# Channel.net
KiCad netlist of a schematic drawn in Altium Designer
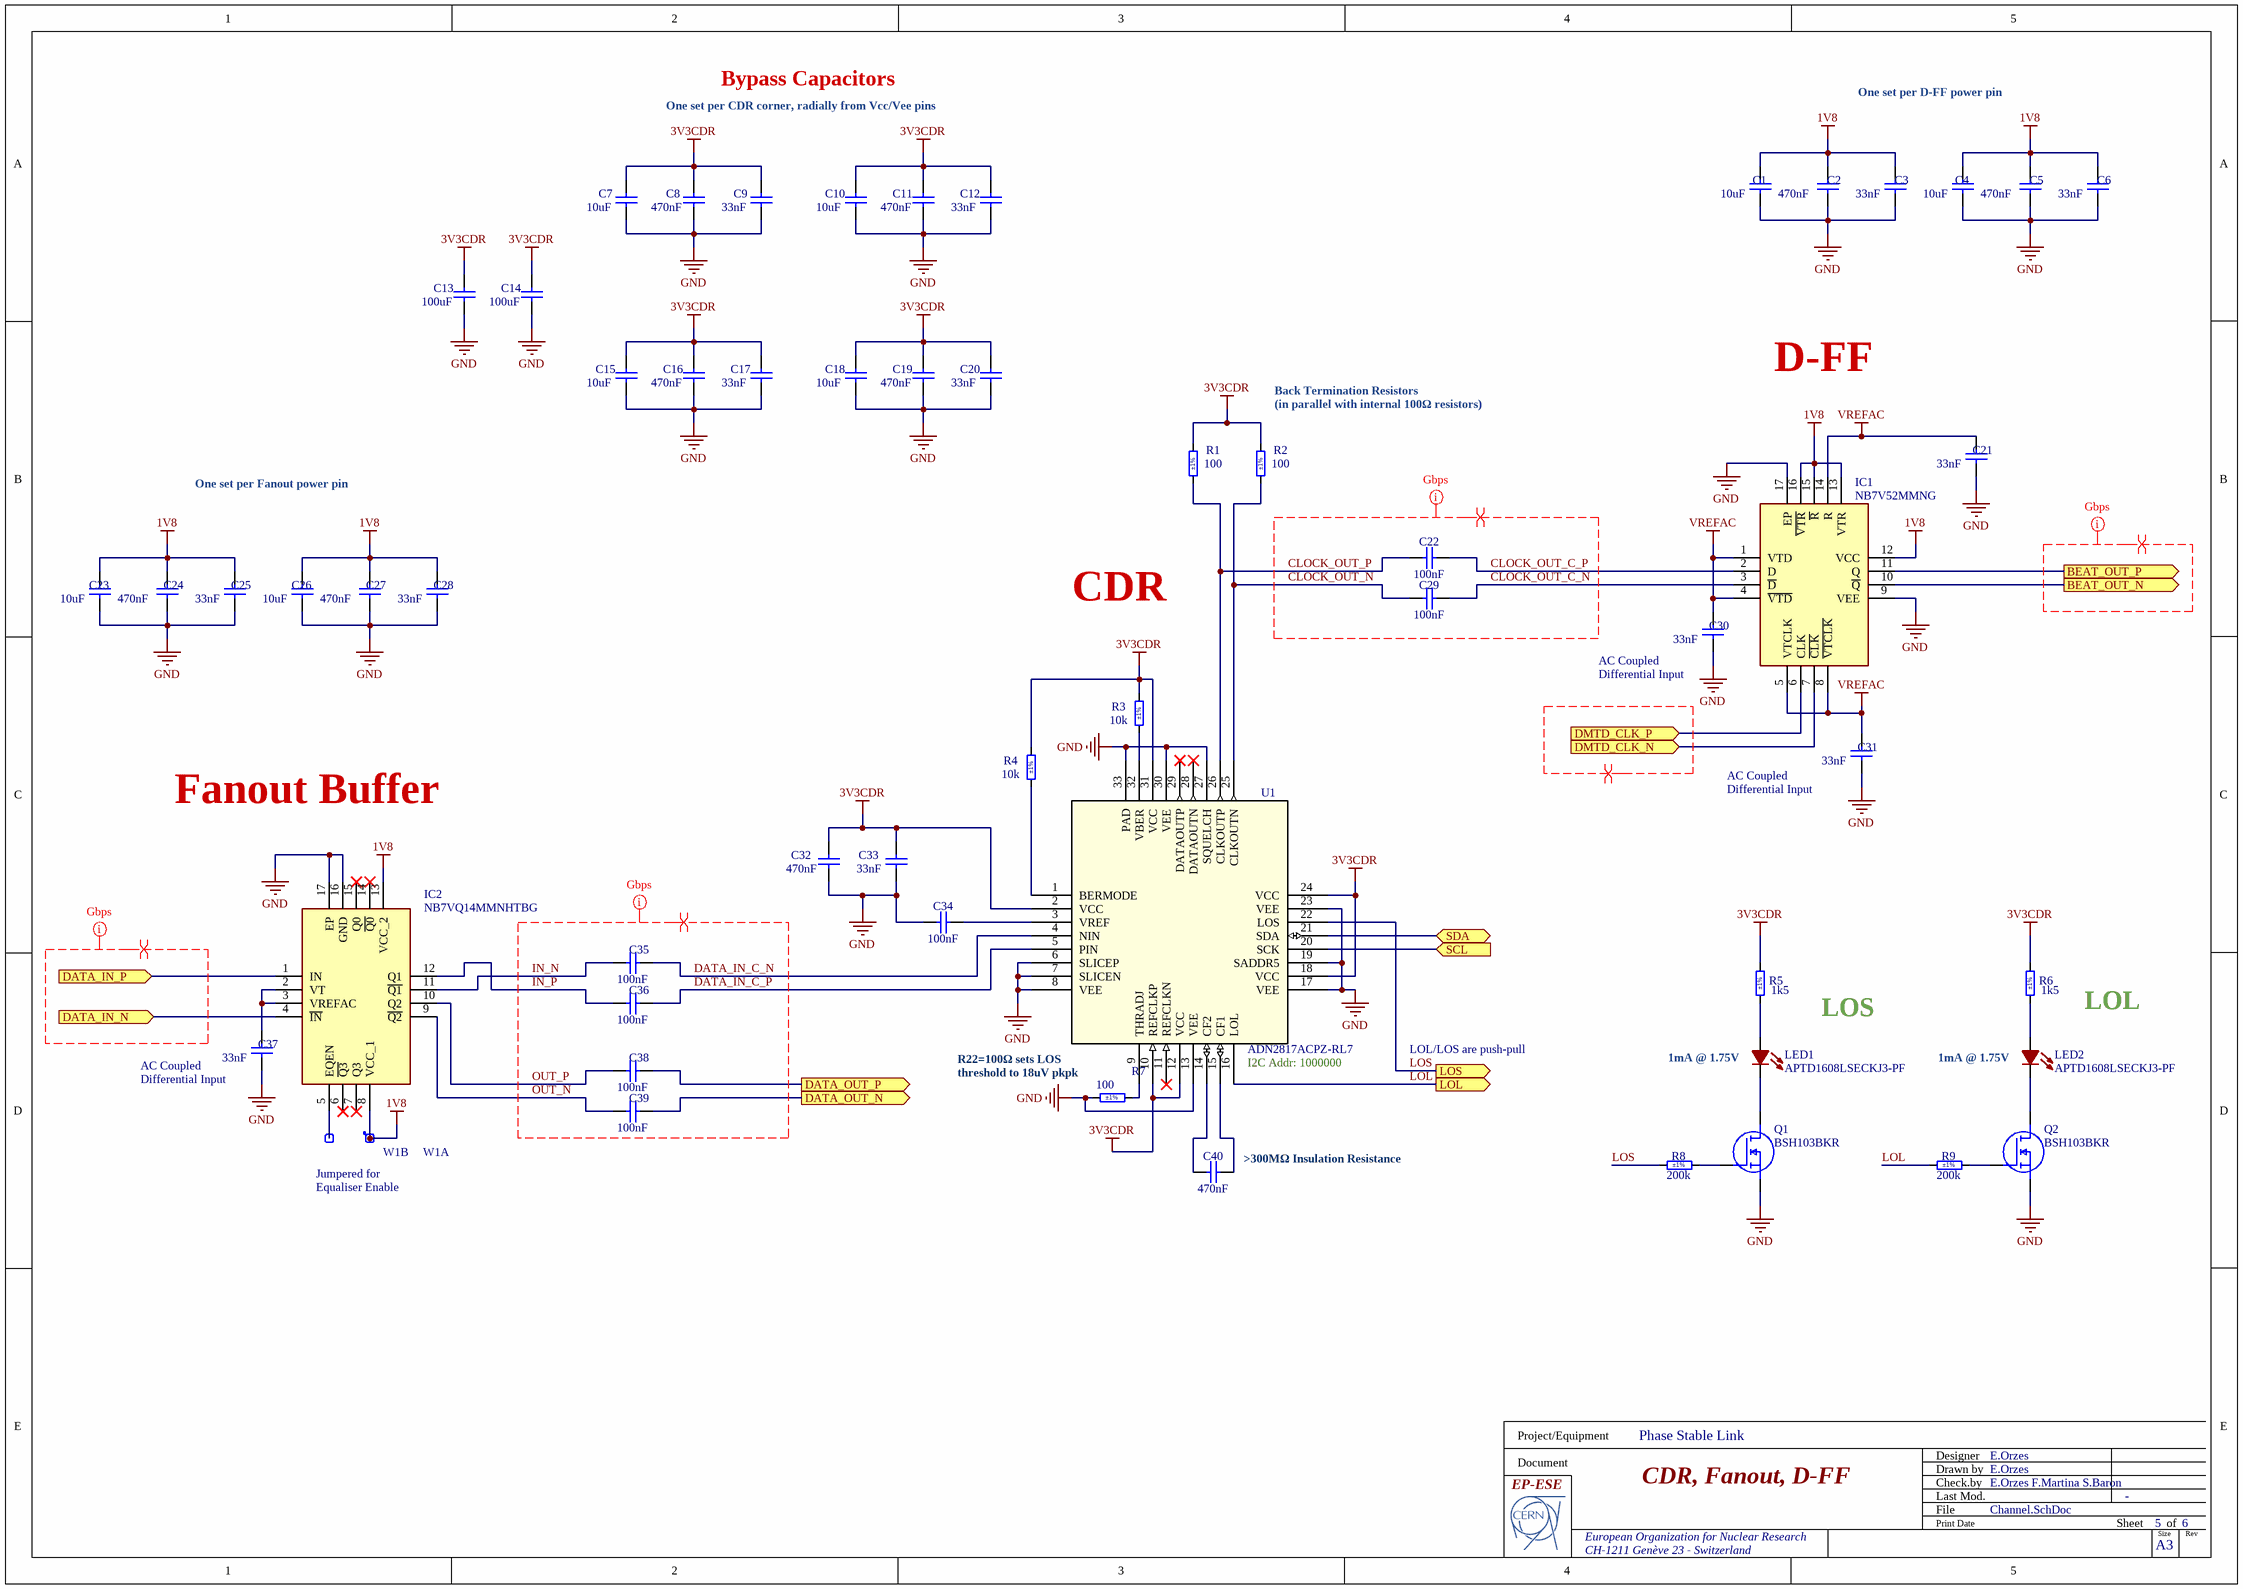
[diagram p0: Channel.SchDoc]

(export (version "E")
  (design (tool "Eeschema 10.0.6"))
  (components
    (comp (ref "C1")
      (value "10uF")
      (footprint "CAPC1608X87N")
      (description "GRM188D71A106KA73")
      (fields
        (field (name "PART NUMBER") "CC0603_10UF_6.3V_20%_X5R")
        (field (name "VOLTAGE") "6.3V")
        (field (name "AUTHOR") "CERN DEM JLC")
      )
      (libsource (lib "Capacitors") (part "Capacitor - non polarized"))
    )
    (comp (ref "C2")
      (value "470nF")
      (footprint "CAPC0510X04N")
      (description "LLL153C70G474ME17")
      (libsource (lib "auxiliary_library") (part "Capacitor - non polarized"))
    )
    (comp (ref "C3")
      (value "33nF")
      (footprint "LLL03TR61E333KE01")
      (description "LLL03TR61E333KE01")
      (libsource (lib "auxiliary_library") (part "Capacitor - non polarized"))
    )
    (comp (ref "C4")
      (value "10uF")
      (footprint "CAPC1608X87N")
      (description "GRM188D71A106KA73")
      (fields
        (field (name "PART NUMBER") "CC0603_10UF_6.3V_20%_X5R")
        (field (name "VOLTAGE") "6.3V")
        (field (name "AUTHOR") "CERN DEM JLC")
      )
      (libsource (lib "Capacitors") (part "Capacitor - non polarized"))
    )
    (comp (ref "C5")
      (value "470nF")
      (footprint "CAPC0510X04N")
      (description "LLL153C70G474ME17")
      (libsource (lib "auxiliary_library") (part "Capacitor - non polarized"))
    )
    (comp (ref "C6")
      (value "33nF")
      (footprint "LLL03TR61E333KE01")
      (description "LLL03TR61E333KE01")
      (libsource (lib "auxiliary_library") (part "Capacitor - non polarized"))
    )
    (comp (ref "C7")
      (value "10uF")
      (footprint "CAPC1608X87N")
      (description "GRM188D71A106KA73")
      (fields
        (field (name "PART NUMBER") "CC0603_10UF_6.3V_20%_X5R")
        (field (name "VOLTAGE") "6.3V")
        (field (name "AUTHOR") "CERN DEM JLC")
      )
      (libsource (lib "Capacitors") (part "Capacitor - non polarized"))
    )
    (comp (ref "C8")
      (value "470nF")
      (footprint "CAPC0510X04N")
      (description "LLL153C70G474ME17")
      (libsource (lib "auxiliary_library") (part "Capacitor - non polarized"))
    )
    (comp (ref "C9")
      (value "33nF")
      (footprint "LLL03TR61E333KE01")
      (description "LLL03TR61E333KE01")
      (libsource (lib "auxiliary_library") (part "Capacitor - non polarized"))
    )
    (comp (ref "C10")
      (value "10uF")
      (footprint "CAPC1608X87N")
      (description "GRM188D71A106KA73")
      (fields
        (field (name "PART NUMBER") "CC0603_10UF_6.3V_20%_X5R")
        (field (name "VOLTAGE") "6.3V")
        (field (name "AUTHOR") "CERN DEM JLC")
      )
      (libsource (lib "Capacitors") (part "Capacitor - non polarized"))
    )
    (comp (ref "C11")
      (value "470nF")
      (footprint "CAPC0510X04N")
      (description "LLL153C70G474ME17")
      (libsource (lib "auxiliary_library") (part "Capacitor - non polarized"))
    )
    (comp (ref "C12")
      (value "33nF")
      (footprint "LLL03TR61E333KE01")
      (description "LLL03TR61E333KE01")
      (libsource (lib "auxiliary_library") (part "Capacitor - non polarized"))
    )
    (comp (ref "C13")
      (value "100uF")
      (footprint "CAPC3225X270N")
      (description "GRM32EC70J107ME15")
      (fields
        (field (name "PART NUMBER") "CC1210_100UF_6.3V_20%_X7U")
        (field (name "VOLTAGE") "6.3V")
        (field (name "AUTHOR") "CERN DEM MR")
      )
      (libsource (lib "Capacitors") (part "Capacitor - non polarized"))
    )
    (comp (ref "C14")
      (value "100uF")
      (footprint "CAPC3225X270N")
      (description "GRM32EC70J107ME15")
      (fields
        (field (name "PART NUMBER") "CC1210_100UF_6.3V_20%_X7U")
        (field (name "VOLTAGE") "6.3V")
        (field (name "AUTHOR") "CERN DEM MR")
      )
      (libsource (lib "Capacitors") (part "Capacitor - non polarized"))
    )
    (comp (ref "C15")
      (value "10uF")
      (footprint "CAPC1608X87N")
      (description "GRM188D71A106KA73")
      (fields
        (field (name "PART NUMBER") "CC0603_10UF_6.3V_20%_X5R")
        (field (name "VOLTAGE") "6.3V")
        (field (name "AUTHOR") "CERN DEM JLC")
      )
      (libsource (lib "Capacitors") (part "Capacitor - non polarized"))
    )
    (comp (ref "C16")
      (value "470nF")
      (footprint "CAPC0510X04N")
      (description "LLL153C70G474ME17")
      (libsource (lib "auxiliary_library") (part "Capacitor - non polarized"))
    )
    (comp (ref "C17")
      (value "33nF")
      (footprint "LLL03TR61E333KE01")
      (description "LLL03TR61E333KE01")
      (libsource (lib "auxiliary_library") (part "Capacitor - non polarized"))
    )
    (comp (ref "C18")
      (value "10uF")
      (footprint "CAPC1608X87N")
      (description "GRM188D71A106KA73")
      (fields
        (field (name "PART NUMBER") "CC0603_10UF_6.3V_20%_X5R")
        (field (name "VOLTAGE") "6.3V")
        (field (name "AUTHOR") "CERN DEM JLC")
      )
      (libsource (lib "Capacitors") (part "Capacitor - non polarized"))
    )
    (comp (ref "C19")
      (value "470nF")
      (footprint "CAPC0510X04N")
      (description "LLL153C70G474ME17")
      (libsource (lib "auxiliary_library") (part "Capacitor - non polarized"))
    )
    (comp (ref "C20")
      (value "33nF")
      (footprint "LLL03TR61E333KE01")
      (description "LLL03TR61E333KE01")
      (libsource (lib "auxiliary_library") (part "Capacitor - non polarized"))
    )
    (comp (ref "C21")
      (value "33nF")
      (footprint "LLL03TR61E333KE01")
      (description "LLL03TR61E333KE01")
      (libsource (lib "auxiliary_library") (part "Capacitor - non polarized"))
    )
    (comp (ref "C22")
      (value "100nF")
      (footprint "CAPC0603X33N")
      (description "Non-polarised capacitor")
      (fields
        (field (name "PART NUMBER") "CC0201_100NF_6.3V_10%_X7R")
        (field (name "VOLTAGE") "6.3V")
        (field (name "AUTHOR") "CERN DEM BC")
      )
      (libsource (lib "Capacitors") (part "Capacitor - non polarized"))
    )
    (comp (ref "C23")
      (value "10uF")
      (footprint "CAPC1608X87N")
      (description "GRM188D71A106KA73")
      (fields
        (field (name "PART NUMBER") "CC0603_10UF_6.3V_20%_X5R")
        (field (name "VOLTAGE") "6.3V")
        (field (name "AUTHOR") "CERN DEM JLC")
      )
      (libsource (lib "Capacitors") (part "Capacitor - non polarized"))
    )
    (comp (ref "C24")
      (value "470nF")
      (footprint "CAPC0510X04N")
      (description "LLL153C70G474ME17")
      (libsource (lib "auxiliary_library") (part "Capacitor - non polarized"))
    )
    (comp (ref "C25")
      (value "33nF")
      (footprint "LLL03TR61E333KE01")
      (description "LLL03TR61E333KE01")
      (libsource (lib "auxiliary_library") (part "Capacitor - non polarized"))
    )
    (comp (ref "C26")
      (value "10uF")
      (footprint "CAPC1608X87N")
      (description "GRM188D71A106KA73")
      (fields
        (field (name "PART NUMBER") "CC0603_10UF_6.3V_20%_X5R")
        (field (name "VOLTAGE") "6.3V")
        (field (name "AUTHOR") "CERN DEM JLC")
      )
      (libsource (lib "Capacitors") (part "Capacitor - non polarized"))
    )
    (comp (ref "C27")
      (value "470nF")
      (footprint "CAPC0510X04N")
      (description "LLL153C70G474ME17")
      (libsource (lib "auxiliary_library") (part "Capacitor - non polarized"))
    )
    (comp (ref "C28")
      (value "33nF")
      (footprint "LLL03TR61E333KE01")
      (description "LLL03TR61E333KE01")
      (libsource (lib "auxiliary_library") (part "Capacitor - non polarized"))
    )
    (comp (ref "C29")
      (value "100nF")
      (footprint "CAPC0603X33N")
      (description "Non-polarised capacitor")
      (fields
        (field (name "PART NUMBER") "CC0201_100NF_6.3V_10%_X7R")
        (field (name "VOLTAGE") "6.3V")
        (field (name "AUTHOR") "CERN DEM BC")
      )
      (libsource (lib "Capacitors") (part "Capacitor - non polarized"))
    )
    (comp (ref "C30")
      (value "33nF")
      (footprint "LLL03TR61E333KE01")
      (description "LLL03TR61E333KE01")
      (libsource (lib "auxiliary_library") (part "Capacitor - non polarized"))
    )
    (comp (ref "C31")
      (value "33nF")
      (footprint "LLL03TR61E333KE01")
      (description "LLL03TR61E333KE01")
      (libsource (lib "auxiliary_library") (part "Capacitor - non polarized"))
    )
    (comp (ref "C32")
      (value "470nF")
      (footprint "CAPC0510X04N")
      (description "LLL153C70G474ME17")
      (libsource (lib "auxiliary_library") (part "Capacitor - non polarized"))
    )
    (comp (ref "C33")
      (value "33nF")
      (footprint "LLL03TR61E333KE01")
      (description "LLL03TR61E333KE01")
      (libsource (lib "auxiliary_library") (part "Capacitor - non polarized"))
    )
    (comp (ref "C34")
      (value "100nF")
      (footprint "CAPC0603X33N")
      (description "Non-polarised capacitor")
      (fields
        (field (name "PART NUMBER") "CC0201_100NF_6.3V_10%_X7R")
        (field (name "VOLTAGE") "6.3V")
        (field (name "AUTHOR") "CERN DEM BC")
      )
      (libsource (lib "Capacitors") (part "Capacitor - non polarized"))
    )
    (comp (ref "C35")
      (value "100nF")
      (footprint "CAPC0603X33N")
      (description "Non-polarised capacitor")
      (fields
        (field (name "PART NUMBER") "CC0201_100NF_6.3V_10%_X7R")
        (field (name "VOLTAGE") "6.3V")
        (field (name "AUTHOR") "CERN DEM BC")
      )
      (libsource (lib "Capacitors") (part "Capacitor - non polarized"))
    )
    (comp (ref "C36")
      (value "100nF")
      (footprint "CAPC0603X33N")
      (description "Non-polarised capacitor")
      (fields
        (field (name "PART NUMBER") "CC0201_100NF_6.3V_10%_X7R")
        (field (name "VOLTAGE") "6.3V")
        (field (name "AUTHOR") "CERN DEM BC")
      )
      (libsource (lib "Capacitors") (part "Capacitor - non polarized"))
    )
    (comp (ref "C37")
      (value "33nF")
      (footprint "LLL03TR61E333KE01")
      (description "LLL03TR61E333KE01")
      (libsource (lib "auxiliary_library") (part "Capacitor - non polarized"))
    )
    (comp (ref "C38")
      (value "100nF")
      (footprint "CAPC0603X33N")
      (description "Non-polarised capacitor")
      (fields
        (field (name "PART NUMBER") "CC0201_100NF_6.3V_10%_X7R")
        (field (name "VOLTAGE") "6.3V")
        (field (name "AUTHOR") "CERN DEM BC")
      )
      (libsource (lib "Capacitors") (part "Capacitor - non polarized"))
    )
    (comp (ref "C39")
      (value "100nF")
      (footprint "CAPC0603X33N")
      (description "Non-polarised capacitor")
      (fields
        (field (name "PART NUMBER") "CC0201_100NF_6.3V_10%_X7R")
        (field (name "VOLTAGE") "6.3V")
        (field (name "AUTHOR") "CERN DEM BC")
      )
      (libsource (lib "Capacitors") (part "Capacitor - non polarized"))
    )
    (comp (ref "C40")
      (value "470nF")
      (footprint "CAPC2013X140N")
      (description "GCM21BR71H474KA55L")
      (fields
        (field (name "PART NUMBER") "CC0805_470NF_50V_10%_X7R_MURATA_GCM21BR71H474KA55L")
        (field (name "VOLTAGE") "50V")
        (field (name "AUTHOR") "CERN DEM JLC")
      )
      (libsource (lib "Capacitors") (part "Capacitor - non polarized"))
    )
    (comp (ref "IC1")
      (value "NB7V52MMNG")
      (footprint "SamacSys:QFN50P300X300X100-17N")
      (description "Integrated Circuit")
      (fields (field (name "MOUSER PART NUMBER") "863-NB7V52MMNG"))
      (libsource (lib "SamacSys") (part "NB7V52MMNG"))
    )
    (comp (ref "IC2")
      (value "NB7VQ14MMNHTBG")
      (footprint "SamacSys:QFN50P300X300X100-17N")
      (description "Integrated Circuit")
      (fields (field (name "MOUSER PART NUMBER") "863-NB7VQ14MMNHTBG"))
      (libsource (lib "*") (part "NB7VQ14MMNHTBG"))
    )
    (comp (ref "LED1")
      (value "APTD1608LSECKJ3-PF")
      (footprint "APTD1608LSECKJ3-PF:LED_APTD1608LSECKJ3-PF_KNB")
      (description "Led Red 0603 2mA 1.8V 50mcd 84mW")
      (libsource (lib "APTD1608LSECKJ3-PF") (part "APTD1608LSECKJ3-PF"))
    )
    (comp (ref "LED2")
      (value "APTD1608LSECKJ3-PF")
      (footprint "APTD1608LSECKJ3-PF:LED_APTD1608LSECKJ3-PF_KNB")
      (description "Led Red 0603 2mA 1.8V 50mcd 84mW")
      (libsource (lib "APTD1608LSECKJ3-PF") (part "APTD1608LSECKJ3-PF"))
    )
    (comp (ref "Q1")
      (value "BSH103BKR")
      (footprint "SamacSys:SOT95P230X110-3N")
      (description "MOSFET (N-Channel)")
      (fields (field (name "MOUSER PART NUMBER") "771-BSH103BKR"))
      (libsource (lib "SamacSys") (part "BSH103BKR"))
    )
    (comp (ref "Q2")
      (value "BSH103BKR")
      (footprint "SamacSys:SOT95P230X110-3N")
      (description "MOSFET (N-Channel)")
      (fields (field (name "MOUSER PART NUMBER") "771-BSH103BKR"))
      (libsource (lib "SamacSys") (part "BSH103BKR"))
    )
    (comp (ref "R1")
      (value "100")
      (footprint "RESC0603X28N")
      (description "Resistor - 1%")
      (fields
        (field (name "TOLERANCE") "±1%")
        (field (name "PART NUMBER") "R0201_100R_1%_0.05W_200PPM")
        (field (name "POWER") "0.05W")
        (field (name "AUTHOR") "CERN DEM JLC")
      )
      (libsource (lib "Resistors") (part "Resistor - 1%"))
    )
    (comp (ref "R2")
      (value "100")
      (footprint "RESC0603X28N")
      (description "Resistor - 1%")
      (fields
        (field (name "TOLERANCE") "±1%")
        (field (name "PART NUMBER") "R0201_100R_1%_0.05W_200PPM")
        (field (name "POWER") "0.05W")
        (field (name "AUTHOR") "CERN DEM JLC")
      )
      (libsource (lib "Resistors") (part "Resistor - 1%"))
    )
    (comp (ref "R3")
      (value "10k")
      (footprint "RESC1005X40N")
      (description "Resistor - 1%")
      (fields
        (field (name "TOLERANCE") "±1%")
        (field (name "PART NUMBER") "R0402_10K_1%_0.0625W_100PPM")
        (field (name "POWER") "0.0625W")
        (field (name "AUTHOR") "CERN DEM JLC")
      )
      (libsource (lib "Resistors") (part "Resistor - 1%"))
    )
    (comp (ref "R4")
      (value "10k")
      (footprint "RESC1005X40N")
      (description "Resistor - 1%")
      (fields
        (field (name "TOLERANCE") "±1%")
        (field (name "PART NUMBER") "R0402_10K_1%_0.0625W_100PPM")
        (field (name "POWER") "0.0625W")
        (field (name "AUTHOR") "CERN DEM JLC")
      )
      (libsource (lib "Resistors") (part "Resistor - 1%"))
    )
    (comp (ref "R5")
      (value "1k5")
      (footprint "RESC1005X40N")
      (description "Resistor - 1%")
      (fields
        (field (name "TOLERANCE") "±1%")
        (field (name "PART NUMBER") "R0402_1K5_1%_0.0625W_100PPM")
        (field (name "POWER") "0.0625W")
        (field (name "AUTHOR") "CERN DEM JLC")
      )
      (libsource (lib "Resistors") (part "Resistor - 1%"))
    )
    (comp (ref "R6")
      (value "1k5")
      (footprint "RESC1005X40N")
      (description "Resistor - 1%")
      (fields
        (field (name "TOLERANCE") "±1%")
        (field (name "PART NUMBER") "R0402_1K5_1%_0.0625W_100PPM")
        (field (name "POWER") "0.0625W")
        (field (name "AUTHOR") "CERN DEM JLC")
      )
      (libsource (lib "Resistors") (part "Resistor - 1%"))
    )
    (comp (ref "R7")
      (value "100")
      (footprint "RESC0603X28N")
      (description "Resistor - 1%")
      (fields
        (field (name "TOLERANCE") "±1%")
        (field (name "PART NUMBER") "R0201_100R_1%_0.05W_200PPM")
        (field (name "POWER") "0.05W")
        (field (name "AUTHOR") "CERN DEM JLC")
      )
      (libsource (lib "Resistors") (part "Resistor - 1%"))
    )
    (comp (ref "R8")
      (value "200k")
      (footprint "RESC1005X40N")
      (description "Resistor - 1%")
      (fields
        (field (name "TOLERANCE") "±1%")
        (field (name "PART NUMBER") "R0402_200K_1%_0.0625W_100PPM")
        (field (name "POWER") "0.0625W")
        (field (name "AUTHOR") "CERN DEM JLC")
      )
      (libsource (lib "Resistors") (part "Resistor - 1%"))
    )
    (comp (ref "R9")
      (value "200k")
      (footprint "RESC1005X40N")
      (description "Resistor - 1%")
      (fields
        (field (name "TOLERANCE") "±1%")
        (field (name "PART NUMBER") "R0402_200K_1%_0.0625W_100PPM")
        (field (name "POWER") "0.0625W")
        (field (name "AUTHOR") "CERN DEM JLC")
      )
      (libsource (lib "Resistors") (part "Resistor - 1%"))
    )
    (comp (ref "U1")
      (value "ADN2817ACPZ-RL7")
      (footprint "CP_32_11_ADI")
      (description "No Description Available")
      (libsource (lib "ADN2817ACPZ-RL7") (part "ADN2817ACPZ-RL7"))
    )
    (comp (ref "W1")
      (value "Header 2")
      (footprint "SAMTEC_HTSW-102-23-L-S")
      (description "2 Mini Wire-Wrap Contact Strip Header")
      (fields
        (field (name "PART NUMBER") "SAMTEC_HTSW-102-23-L-S")
        (field (name "MANUFACTURER") "SAMTEC")
        (field (name "AUTHOR") "CERN DEM JLC")
      )
      (libsource (lib "Connectors") (part "Wire-Wrap Contact x2"))
    )
  )
  (nets
    (net (code "1") (name "/BEAT_OUT_N") (class "Default")
      (node (ref "IC1") (pin "10") (pinfunction "~{Q}_10") (pintype "passive"))
    )
    (net (code "2") (name "/BEAT_OUT_P") (class "Default")
      (node (ref "IC1") (pin "11") (pinfunction "Q_11") (pintype "passive"))
    )
    (net (code "3") (name "/CLOCK_OUT_C_N") (class "Default")
      (node (ref "C29") (pin "2") (pinfunction "2_2") (pintype "passive"))
      (node (ref "IC1") (pin "3") (pinfunction "~{D}_3") (pintype "passive"))
    )
    (net (code "4") (name "/CLOCK_OUT_C_P") (class "Default")
      (node (ref "C22") (pin "2") (pinfunction "2_2") (pintype "passive"))
      (node (ref "IC1") (pin "2") (pinfunction "D_2") (pintype "passive"))
    )
    (net (code "5") (name "/CLOCK_OUT_N") (class "Default")
      (node (ref "C29") (pin "1") (pinfunction "1_1") (pintype "passive"))
      (node (ref "R2") (pin "1") (pinfunction "1_1") (pintype "passive"))
      (node (ref "U1") (pin "25") (pinfunction "CLKOUTN_25") (pintype "output"))
    )
    (net (code "6") (name "/CLOCK_OUT_P") (class "Default")
      (node (ref "C22") (pin "1") (pinfunction "1_1") (pintype "passive"))
      (node (ref "R1") (pin "1") (pinfunction "1_1") (pintype "passive"))
      (node (ref "U1") (pin "26") (pinfunction "CLKOUTP_26") (pintype "output"))
    )
    (net (code "7") (name "/DATA_IN_C_N") (class "Default")
      (node (ref "C35") (pin "2") (pinfunction "2_2") (pintype "passive"))
      (node (ref "U1") (pin "4") (pinfunction "NIN_4") (pintype "passive"))
    )
    (net (code "8") (name "/DATA_IN_C_P") (class "Default")
      (node (ref "C36") (pin "2") (pinfunction "2_2") (pintype "passive"))
      (node (ref "U1") (pin "5") (pinfunction "PIN_5") (pintype "passive"))
    )
    (net (code "9") (name "/DATA_IN_N") (class "Default")
      (node (ref "IC2") (pin "4") (pinfunction "~{IN}_4") (pintype "passive"))
    )
    (net (code "10") (name "/DATA_IN_P") (class "Default")
      (node (ref "IC2") (pin "1") (pinfunction "IN_1") (pintype "passive"))
    )
    (net (code "11") (name "/DATA_OUT_N") (class "Default")
      (node (ref "C39") (pin "2") (pinfunction "2_2") (pintype "passive"))
    )
    (net (code "12") (name "/DATA_OUT_P") (class "Default")
      (node (ref "C38") (pin "2") (pinfunction "2_2") (pintype "passive"))
    )
    (net (code "13") (name "/DMTD_CLK_N") (class "Default")
      (node (ref "IC1") (pin "7") (pinfunction "~{CLK}_7") (pintype "passive"))
    )
    (net (code "14") (name "/DMTD_CLK_P") (class "Default")
      (node (ref "IC1") (pin "6") (pinfunction "CLK_6") (pintype "passive"))
    )
    (net (code "15") (name "/IN_N") (class "Default")
      (node (ref "C35") (pin "1") (pinfunction "1_1") (pintype "passive"))
      (node (ref "IC2") (pin "11") (pinfunction "~{Q1}_11") (pintype "passive"))
    )
    (net (code "16") (name "/IN_P") (class "Default")
      (node (ref "C36") (pin "1") (pinfunction "1_1") (pintype "passive"))
      (node (ref "IC2") (pin "12") (pinfunction "Q1_12") (pintype "passive"))
    )
    (net (code "17") (name "/LOL") (class "Default")
      (node (ref "R9") (pin "1") (pinfunction "1_1") (pintype "passive"))
      (node (ref "U1") (pin "16") (pinfunction "LOL_16") (pintype "passive"))
    )
    (net (code "18") (name "/LOS") (class "Default")
      (node (ref "R8") (pin "1") (pinfunction "1_1") (pintype "passive"))
      (node (ref "U1") (pin "22") (pinfunction "LOS_22") (pintype "passive"))
    )
    (net (code "19") (name "/OUT_N") (class "Default")
      (node (ref "C39") (pin "1") (pinfunction "1_1") (pintype "passive"))
      (node (ref "IC2") (pin "9") (pinfunction "~{Q2}_9") (pintype "passive"))
    )
    (net (code "20") (name "/OUT_P") (class "Default")
      (node (ref "C38") (pin "1") (pinfunction "1_1") (pintype "passive"))
      (node (ref "IC2") (pin "10") (pinfunction "Q2_10") (pintype "passive"))
    )
    (net (code "21") (name "/SCL") (class "Default")
      (node (ref "U1") (pin "20") (pinfunction "SCK_20") (pintype "passive"))
    )
    (net (code "22") (name "/SDA") (class "Default")
      (node (ref "U1") (pin "21") (pinfunction "SDA_21") (pintype "bidirectional"))
    )
    (net (code "23") (name "1V8") (class "Default")
      (node (ref "C1") (pin "2") (pinfunction "2_2") (pintype "passive"))
      (node (ref "C2") (pin "2") (pinfunction "2_2") (pintype "passive"))
      (node (ref "C23") (pin "2") (pinfunction "2_2") (pintype "passive"))
      (node (ref "C24") (pin "2") (pinfunction "2_2") (pintype "passive"))
      (node (ref "C25") (pin "2") (pinfunction "2_2") (pintype "passive"))
      (node (ref "C26") (pin "2") (pinfunction "2_2") (pintype "passive"))
      (node (ref "C27") (pin "2") (pinfunction "2_2") (pintype "passive"))
      (node (ref "C28") (pin "2") (pinfunction "2_2") (pintype "passive"))
      (node (ref "C3") (pin "2") (pinfunction "2_2") (pintype "passive"))
      (node (ref "C4") (pin "2") (pinfunction "2_2") (pintype "passive"))
      (node (ref "C5") (pin "2") (pinfunction "2_2") (pintype "passive"))
      (node (ref "C6") (pin "2") (pinfunction "2_2") (pintype "passive"))
      (node (ref "IC1") (pin "12") (pinfunction "VCC_12") (pintype "passive"))
      (node (ref "IC1") (pin "13") (pinfunction "VTR_13") (pintype "passive"))
      (node (ref "IC1") (pin "15") (pinfunction "~{R}_15") (pintype "passive"))
      (node (ref "IC1") (pin "16") (pinfunction "~{VTR}_16") (pintype "passive"))
      (node (ref "IC2") (pin "13") (pinfunction "VCC_2_13") (pintype "passive"))
      (node (ref "IC2") (pin "8") (pinfunction "VCC_1_8") (pintype "passive"))
      (node (ref "W1") (pin "1") (pinfunction "1_1") (pintype "bidirectional"))
    )
    (net (code "24") (name "3V3CDR") (class "Default")
      (node (ref "C10") (pin "2") (pinfunction "2_2") (pintype "passive"))
      (node (ref "C11") (pin "2") (pinfunction "2_2") (pintype "passive"))
      (node (ref "C12") (pin "2") (pinfunction "2_2") (pintype "passive"))
      (node (ref "C13") (pin "2") (pinfunction "2_2") (pintype "passive"))
      (node (ref "C14") (pin "2") (pinfunction "2_2") (pintype "passive"))
      (node (ref "C15") (pin "2") (pinfunction "2_2") (pintype "passive"))
      (node (ref "C16") (pin "2") (pinfunction "2_2") (pintype "passive"))
      (node (ref "C17") (pin "2") (pinfunction "2_2") (pintype "passive"))
      (node (ref "C18") (pin "2") (pinfunction "2_2") (pintype "passive"))
      (node (ref "C19") (pin "2") (pinfunction "2_2") (pintype "passive"))
      (node (ref "C20") (pin "2") (pinfunction "2_2") (pintype "passive"))
      (node (ref "C32") (pin "2") (pinfunction "2_2") (pintype "passive"))
      (node (ref "C33") (pin "2") (pinfunction "2_2") (pintype "passive"))
      (node (ref "C7") (pin "2") (pinfunction "2_2") (pintype "passive"))
      (node (ref "C8") (pin "2") (pinfunction "2_2") (pintype "passive"))
      (node (ref "C9") (pin "2") (pinfunction "2_2") (pintype "passive"))
      (node (ref "R1") (pin "2") (pinfunction "2_2") (pintype "passive"))
      (node (ref "R2") (pin "2") (pinfunction "2_2") (pintype "passive"))
      (node (ref "R3") (pin "2") (pinfunction "2_2") (pintype "passive"))
      (node (ref "R4") (pin "2") (pinfunction "2_2") (pintype "passive"))
      (node (ref "R5") (pin "2") (pinfunction "2_2") (pintype "passive"))
      (node (ref "R6") (pin "2") (pinfunction "2_2") (pintype "passive"))
      (node (ref "U1") (pin "10") (pinfunction "REFCLKP_10") (pintype "input"))
      (node (ref "U1") (pin "12") (pinfunction "VCC_12") (pintype "power_in"))
      (node (ref "U1") (pin "18") (pinfunction "VCC_18") (pintype "power_in"))
      (node (ref "U1") (pin "2") (pinfunction "VCC_2") (pintype "power_in"))
      (node (ref "U1") (pin "24") (pinfunction "VCC_24") (pintype "power_in"))
      (node (ref "U1") (pin "31") (pinfunction "VCC_31") (pintype "power_in"))
    )
    (net (code "25") (name "GND") (class "Default")
      (node (ref "C1") (pin "1") (pinfunction "1_1") (pintype "passive"))
      (node (ref "C10") (pin "1") (pinfunction "1_1") (pintype "passive"))
      (node (ref "C11") (pin "1") (pinfunction "1_1") (pintype "passive"))
      (node (ref "C12") (pin "1") (pinfunction "1_1") (pintype "passive"))
      (node (ref "C13") (pin "1") (pinfunction "1_1") (pintype "passive"))
      (node (ref "C14") (pin "1") (pinfunction "1_1") (pintype "passive"))
      (node (ref "C15") (pin "1") (pinfunction "1_1") (pintype "passive"))
      (node (ref "C16") (pin "1") (pinfunction "1_1") (pintype "passive"))
      (node (ref "C17") (pin "1") (pinfunction "1_1") (pintype "passive"))
      (node (ref "C18") (pin "1") (pinfunction "1_1") (pintype "passive"))
      (node (ref "C19") (pin "1") (pinfunction "1_1") (pintype "passive"))
      (node (ref "C2") (pin "1") (pinfunction "1_1") (pintype "passive"))
      (node (ref "C20") (pin "1") (pinfunction "1_1") (pintype "passive"))
      (node (ref "C21") (pin "1") (pinfunction "1_1") (pintype "passive"))
      (node (ref "C23") (pin "1") (pinfunction "1_1") (pintype "passive"))
      (node (ref "C24") (pin "1") (pinfunction "1_1") (pintype "passive"))
      (node (ref "C25") (pin "1") (pinfunction "1_1") (pintype "passive"))
      (node (ref "C26") (pin "1") (pinfunction "1_1") (pintype "passive"))
      (node (ref "C27") (pin "1") (pinfunction "1_1") (pintype "passive"))
      (node (ref "C28") (pin "1") (pinfunction "1_1") (pintype "passive"))
      (node (ref "C3") (pin "1") (pinfunction "1_1") (pintype "passive"))
      (node (ref "C30") (pin "1") (pinfunction "1_1") (pintype "passive"))
      (node (ref "C31") (pin "1") (pinfunction "1_1") (pintype "passive"))
      (node (ref "C32") (pin "1") (pinfunction "1_1") (pintype "passive"))
      (node (ref "C33") (pin "1") (pinfunction "1_1") (pintype "passive"))
      (node (ref "C34") (pin "1") (pinfunction "1_1") (pintype "passive"))
      (node (ref "C37") (pin "1") (pinfunction "1_1") (pintype "passive"))
      (node (ref "C4") (pin "1") (pinfunction "1_1") (pintype "passive"))
      (node (ref "C5") (pin "1") (pinfunction "1_1") (pintype "passive"))
      (node (ref "C6") (pin "1") (pinfunction "1_1") (pintype "passive"))
      (node (ref "C7") (pin "1") (pinfunction "1_1") (pintype "passive"))
      (node (ref "C8") (pin "1") (pinfunction "1_1") (pintype "passive"))
      (node (ref "C9") (pin "1") (pinfunction "1_1") (pintype "passive"))
      (node (ref "IC1") (pin "17") (pinfunction "EP_17") (pintype "passive"))
      (node (ref "IC1") (pin "9") (pinfunction "VEE_9") (pintype "passive"))
      (node (ref "IC2") (pin "16") (pinfunction "GND_16") (pintype "passive"))
      (node (ref "IC2") (pin "17") (pinfunction "EP_17") (pintype "passive"))
      (node (ref "Q1") (pin "2") (pinfunction "S_2") (pintype "passive"))
      (node (ref "Q2") (pin "2") (pinfunction "S_2") (pintype "passive"))
      (node (ref "R7") (pin "1") (pinfunction "1_1") (pintype "passive"))
      (node (ref "U1") (pin "13") (pinfunction "VEE_13") (pintype "power_in"))
      (node (ref "U1") (pin "17") (pinfunction "VEE_17") (pintype "power_in"))
      (node (ref "U1") (pin "19") (pinfunction "SADDR5_19") (pintype "passive"))
      (node (ref "U1") (pin "23") (pinfunction "VEE_23") (pintype "power_in"))
      (node (ref "U1") (pin "27") (pinfunction "SQUELCH_27") (pintype "passive"))
      (node (ref "U1") (pin "30") (pinfunction "VEE_30") (pintype "power_in"))
      (node (ref "U1") (pin "33") (pinfunction "PAD_33") (pintype "power_in"))
      (node (ref "U1") (pin "6") (pinfunction "SLICEP_6") (pintype "passive"))
      (node (ref "U1") (pin "7") (pinfunction "SLICEN_7") (pintype "passive"))
      (node (ref "U1") (pin "8") (pinfunction "VEE_8") (pintype "power_in"))
    )
    (net (code "26") (name "Net-(IC2-EQEN)") (class "Default")
      (node (ref "IC2") (pin "5") (pinfunction "EQEN_5") (pintype "passive"))
      (node (ref "W1") (pin "2") (pinfunction "2_2") (pintype "power_in"))
    )
    (net (code "27") (name "Net-(IC2-VREFAC)") (class "Default")
      (node (ref "C37") (pin "2") (pinfunction "2_2") (pintype "passive"))
      (node (ref "IC2") (pin "2") (pinfunction "VT_2") (pintype "passive"))
      (node (ref "IC2") (pin "3") (pinfunction "VREFAC_3") (pintype "passive"))
    )
    (net (code "28") (name "Net-(LED1-A)") (class "Default")
      (node (ref "LED1") (pin "2") (pinfunction "A_2") (pintype "passive"))
      (node (ref "R5") (pin "1") (pinfunction "1_1") (pintype "passive"))
    )
    (net (code "29") (name "Net-(LED1-C)") (class "Default")
      (node (ref "LED1") (pin "1") (pinfunction "C_1") (pintype "passive"))
      (node (ref "Q1") (pin "3") (pinfunction "D_3") (pintype "passive"))
    )
    (net (code "30") (name "Net-(LED2-A)") (class "Default")
      (node (ref "LED2") (pin "2") (pinfunction "A_2") (pintype "passive"))
      (node (ref "R6") (pin "1") (pinfunction "1_1") (pintype "passive"))
    )
    (net (code "31") (name "Net-(LED2-C)") (class "Default")
      (node (ref "LED2") (pin "1") (pinfunction "C_1") (pintype "passive"))
      (node (ref "Q2") (pin "3") (pinfunction "D_3") (pintype "passive"))
    )
    (net (code "32") (name "Net-(Q1-G)") (class "Default")
      (node (ref "Q1") (pin "1") (pinfunction "G_1") (pintype "passive"))
      (node (ref "R8") (pin "2") (pinfunction "2_2") (pintype "passive"))
    )
    (net (code "33") (name "Net-(Q2-G)") (class "Default")
      (node (ref "Q2") (pin "1") (pinfunction "G_1") (pintype "passive"))
      (node (ref "R9") (pin "2") (pinfunction "2_2") (pintype "passive"))
    )
    (net (code "34") (name "Net-(U1-BERMODE)") (class "Default")
      (node (ref "R4") (pin "1") (pinfunction "1_1") (pintype "passive"))
      (node (ref "U1") (pin "1") (pinfunction "BERMODE_1") (pintype "passive"))
    )
    (net (code "35") (name "Net-(U1-CF1)") (class "Default")
      (node (ref "C40") (pin "2") (pinfunction "2_2") (pintype "passive"))
      (node (ref "U1") (pin "15") (pinfunction "CF1_15") (pintype "bidirectional"))
    )
    (net (code "36") (name "Net-(U1-CF2)") (class "Default")
      (node (ref "C40") (pin "1") (pinfunction "1_1") (pintype "passive"))
      (node (ref "U1") (pin "14") (pinfunction "CF2_14") (pintype "bidirectional"))
    )
    (net (code "37") (name "Net-(U1-THRADJ)") (class "Default")
      (node (ref "R7") (pin "2") (pinfunction "2_2") (pintype "passive"))
      (node (ref "U1") (pin "9") (pinfunction "THRADJ_9") (pintype "passive"))
    )
    (net (code "38") (name "Net-(U1-VBER)") (class "Default")
      (node (ref "R3") (pin "1") (pinfunction "1_1") (pintype "passive"))
      (node (ref "U1") (pin "32") (pinfunction "VBER_32") (pintype "passive"))
    )
    (net (code "39") (name "Net-(U1-VREF)") (class "Default")
      (node (ref "C34") (pin "2") (pinfunction "2_2") (pintype "passive"))
      (node (ref "U1") (pin "3") (pinfunction "VREF_3") (pintype "power_in"))
    )
    (net (code "40") (name "VREFAC") (class "Default")
      (node (ref "C21") (pin "2") (pinfunction "2_2") (pintype "passive"))
      (node (ref "C30") (pin "2") (pinfunction "2_2") (pintype "passive"))
      (node (ref "C31") (pin "2") (pinfunction "2_2") (pintype "passive"))
      (node (ref "IC1") (pin "1") (pinfunction "VTD_1") (pintype "passive"))
      (node (ref "IC1") (pin "14") (pinfunction "R_14") (pintype "passive"))
      (node (ref "IC1") (pin "4") (pinfunction "~{VTD}_4") (pintype "passive"))
      (node (ref "IC1") (pin "5") (pinfunction "VTCLK_5") (pintype "passive"))
      (node (ref "IC1") (pin "8") (pinfunction "~{VTCLK}_8") (pintype "passive"))
    )
    (net (code "41") (name "unconnected-(IC2-Q0-Pad15)") (class "Default")
      (node (ref "IC2") (pin "15") (pinfunction "Q0_15") (pintype "passive+no_connect"))
    )
    (net (code "42") (name "unconnected-(IC2-Q3-Pad7)") (class "Default")
      (node (ref "IC2") (pin "7") (pinfunction "Q3_7") (pintype "passive+no_connect"))
    )
    (net (code "43") (name "unconnected-(IC2-~{Q0}-Pad14)") (class "Default")
      (node (ref "IC2") (pin "14") (pinfunction "~{Q0}_14") (pintype "passive+no_connect"))
    )
    (net (code "44") (name "unconnected-(IC2-~{Q3}-Pad6)") (class "Default")
      (node (ref "IC2") (pin "6") (pinfunction "~{Q3}_6") (pintype "passive+no_connect"))
    )
    (net (code "45") (name "unconnected-(U1-DATAOUTN-Pad28)") (class "Default")
      (node (ref "U1") (pin "28") (pinfunction "DATAOUTN_28") (pintype "output+no_connect"))
    )
    (net (code "46") (name "unconnected-(U1-DATAOUTP-Pad29)") (class "Default")
      (node (ref "U1") (pin "29") (pinfunction "DATAOUTP_29") (pintype "output+no_connect"))
    )
    (net (code "47") (name "unconnected-(U1-REFCLKN-Pad11)") (class "Default")
      (node (ref "U1") (pin "11") (pinfunction "REFCLKN_11") (pintype "input+no_connect"))
    )
  )
)
